# UserInput.net
KiCad netlist of a schematic drawn in Altium Designer
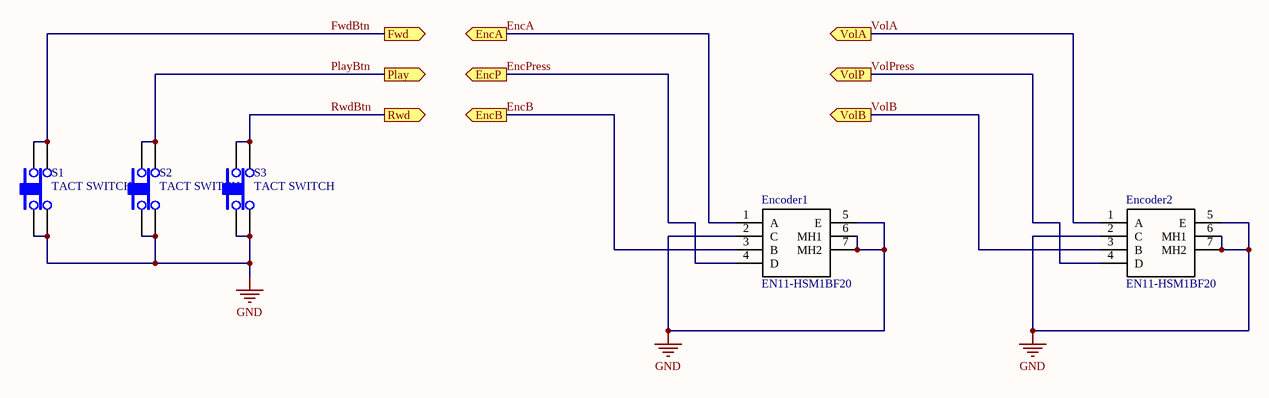
[diagram p0: UserInput.SchDoc]

(export (version "E")
  (design (tool "Eeschema 10.0.6"))
  (components
    (comp (ref "Encoder1")
      (value "EN11-HSM1BF20")
      (footprint "EN11HSM1BF20")
      (description "Switch")
      (libsource (lib "Encoder") (part "EN11-HSM1BF20"))
    )
    (comp (ref "Encoder2")
      (value "EN11-HSM1BF20")
      (footprint "EN11HSM1BF20")
      (description "Switch")
      (libsource (lib "Encoder") (part "EN11-HSM1BF20"))
    )
    (comp (ref "S1")
      (value "TACT SWITCH")
      (footprint "TACTSWITCH")
      (libsource (lib "LIBEBAL") (part "TACT SWITCH"))
    )
    (comp (ref "S2")
      (value "TACT SWITCH")
      (footprint "TACTSWITCH")
      (libsource (lib "LIBEBAL") (part "TACT SWITCH"))
    )
    (comp (ref "S3")
      (value "TACT SWITCH")
      (footprint "TACTSWITCH")
      (libsource (lib "LIBEBAL") (part "TACT SWITCH"))
    )
  )
  (nets
    (net (code "1") (name "/EncA") (class "Default")
      (node (ref "Encoder1") (pin "1") (pinfunction "A_1") (pintype "passive"))
    )
    (net (code "2") (name "/EncB") (class "Default")
      (node (ref "Encoder1") (pin "3") (pinfunction "B_3") (pintype "passive"))
    )
    (net (code "3") (name "/EncPress") (class "Default")
      (node (ref "Encoder1") (pin "4") (pinfunction "D_4") (pintype "passive"))
    )
    (net (code "4") (name "/FwdBtn") (class "Default")
      (node (ref "S1") (pin "3") (pinfunction "3_3") (pintype "passive"))
      (node (ref "S1") (pin "4") (pinfunction "4_4") (pintype "passive"))
    )
    (net (code "5") (name "/PlayBtn") (class "Default")
      (node (ref "S2") (pin "3") (pinfunction "3_3") (pintype "passive"))
      (node (ref "S2") (pin "4") (pinfunction "4_4") (pintype "passive"))
    )
    (net (code "6") (name "/RwdBtn") (class "Default")
      (node (ref "S3") (pin "3") (pinfunction "3_3") (pintype "passive"))
      (node (ref "S3") (pin "4") (pinfunction "4_4") (pintype "passive"))
    )
    (net (code "7") (name "/VolA") (class "Default")
      (node (ref "Encoder2") (pin "1") (pinfunction "A_1") (pintype "passive"))
    )
    (net (code "8") (name "/VolB") (class "Default")
      (node (ref "Encoder2") (pin "3") (pinfunction "B_3") (pintype "passive"))
    )
    (net (code "9") (name "/VolPress") (class "Default")
      (node (ref "Encoder2") (pin "4") (pinfunction "D_4") (pintype "passive"))
    )
    (net (code "10") (name "GND") (class "Default")
      (node (ref "Encoder1") (pin "2") (pinfunction "C_2") (pintype "passive"))
      (node (ref "Encoder1") (pin "5") (pinfunction "E_5") (pintype "passive"))
      (node (ref "Encoder1") (pin "6") (pinfunction "MH1_6") (pintype "passive"))
      (node (ref "Encoder1") (pin "7") (pinfunction "MH2_7") (pintype "passive"))
      (node (ref "Encoder2") (pin "2") (pinfunction "C_2") (pintype "passive"))
      (node (ref "Encoder2") (pin "5") (pinfunction "E_5") (pintype "passive"))
      (node (ref "Encoder2") (pin "6") (pinfunction "MH1_6") (pintype "passive"))
      (node (ref "Encoder2") (pin "7") (pinfunction "MH2_7") (pintype "passive"))
      (node (ref "S1") (pin "1") (pinfunction "1_1") (pintype "passive"))
      (node (ref "S1") (pin "2") (pinfunction "2_2") (pintype "passive"))
      (node (ref "S2") (pin "1") (pinfunction "1_1") (pintype "passive"))
      (node (ref "S2") (pin "2") (pinfunction "2_2") (pintype "passive"))
      (node (ref "S3") (pin "1") (pinfunction "1_1") (pintype "passive"))
      (node (ref "S3") (pin "2") (pinfunction "2_2") (pintype "passive"))
    )
  )
)
